# HDMI.net
KiCad netlist of a schematic drawn in Altium Designer
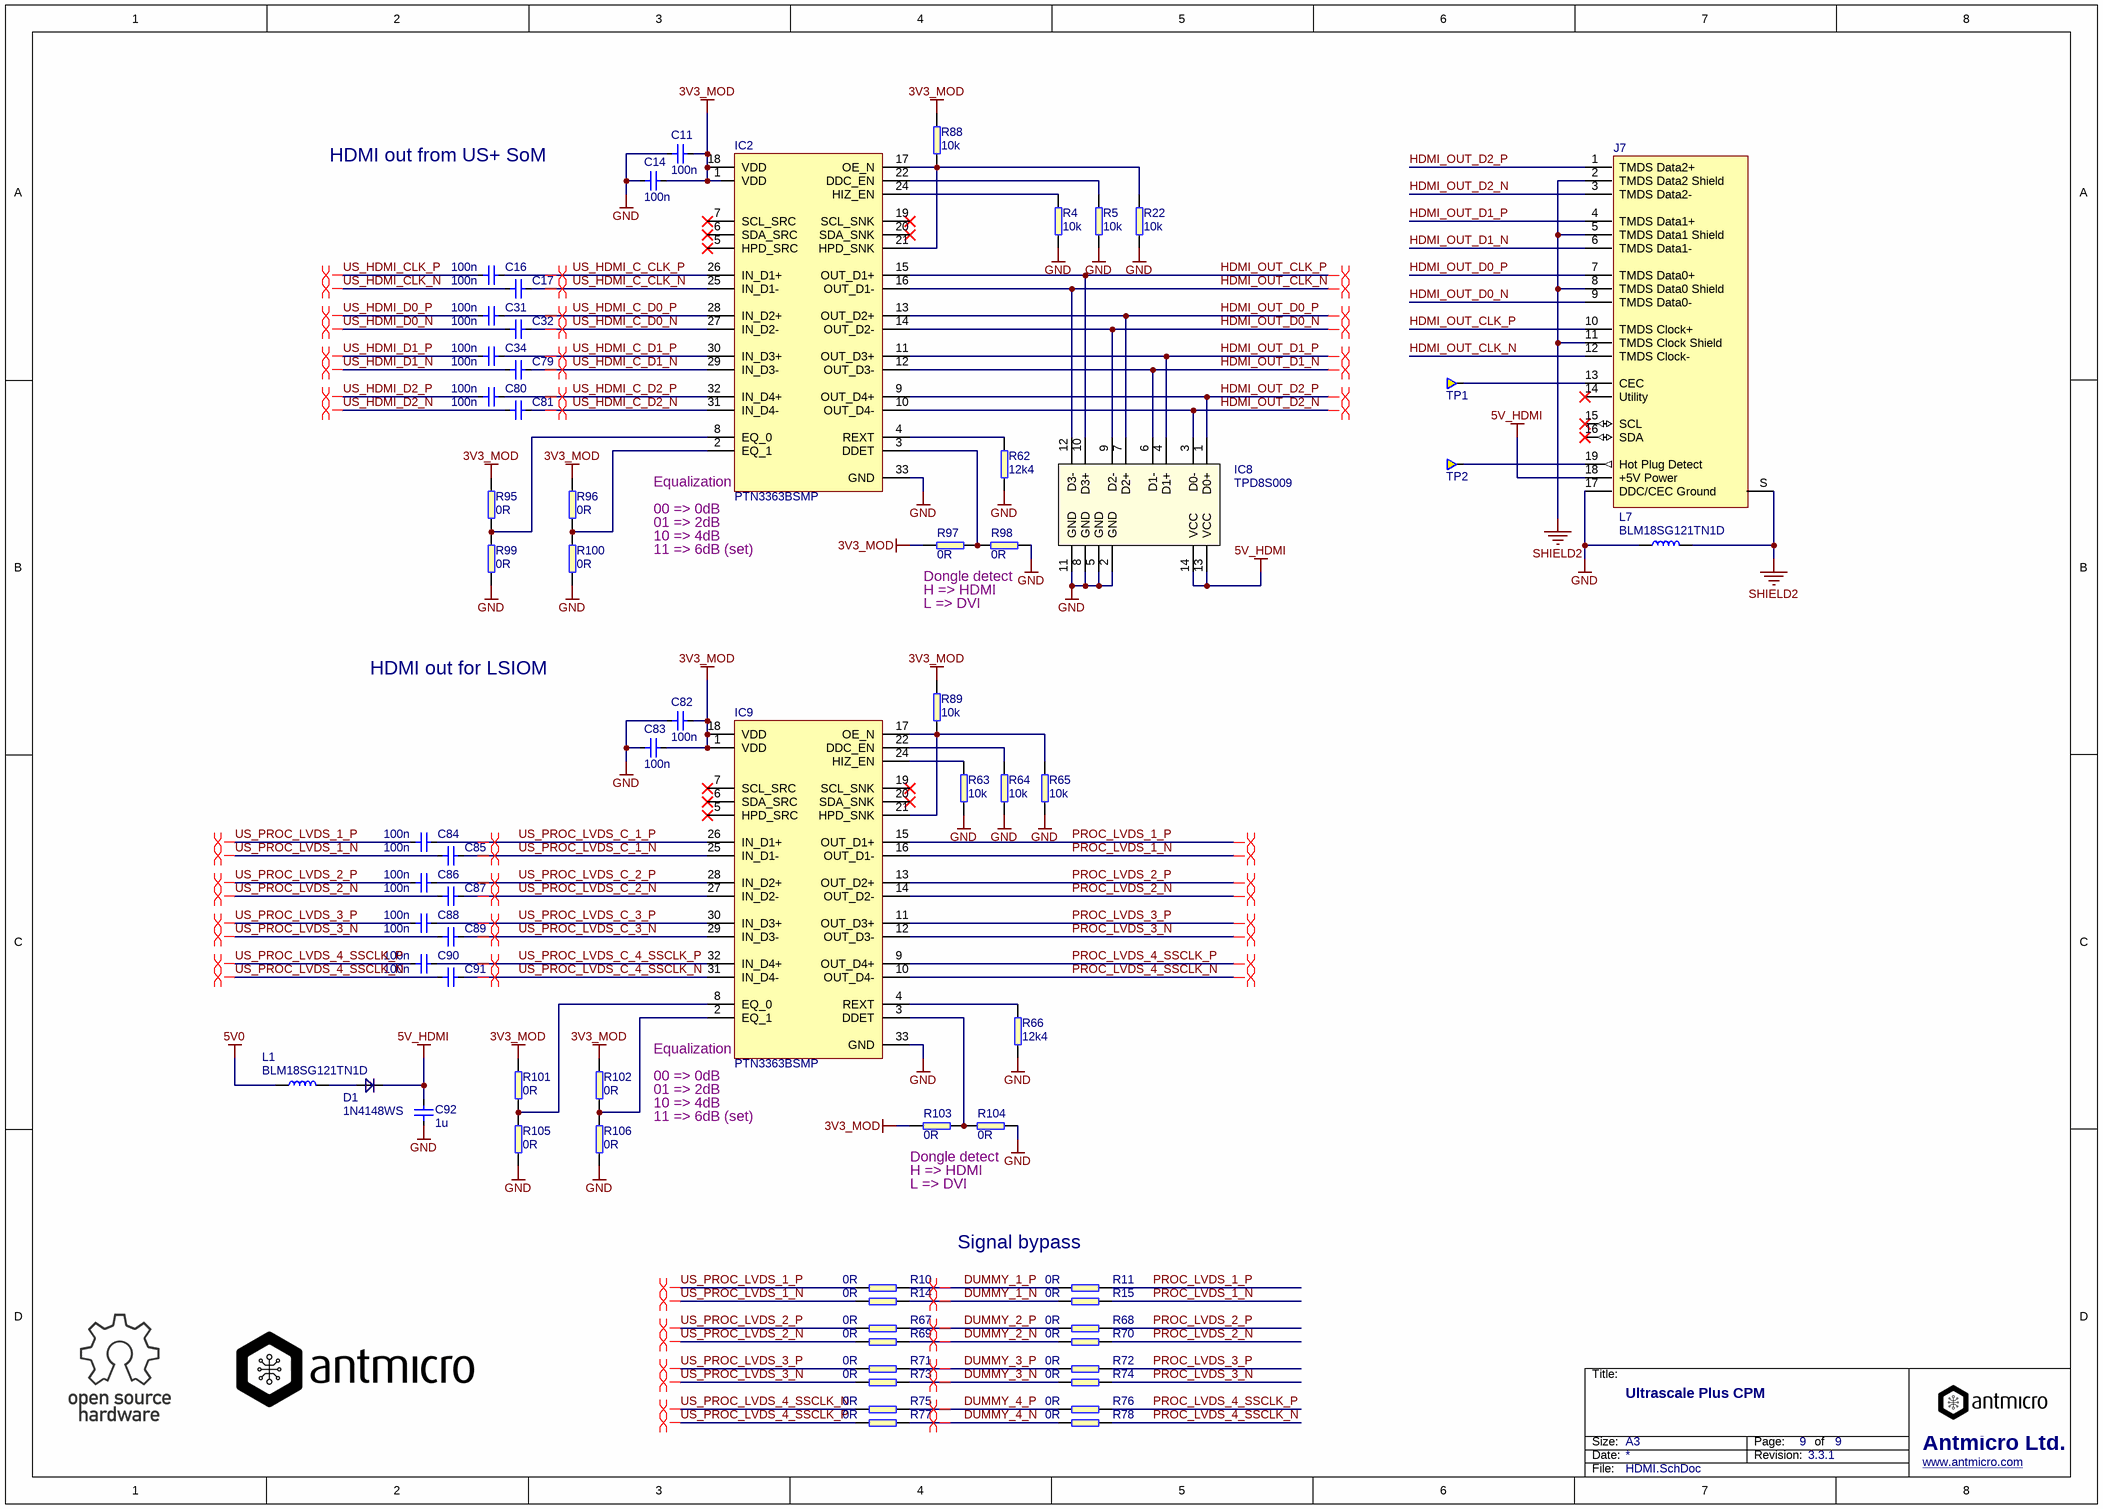
[diagram p0: HDMI.SchDoc]

(export (version "E")
  (design (tool "Eeschema 10.0.6"))
  (components
    (comp (ref "C11")
      (value "100n")
      (footprint "0603")
      (description "MLCC SMT Capacitor 100nF 0603")
      (fields (field (name "PART NUMBER") "C_100n_0603") (field (name "MANUFACTURER") "WALSIN"))
      (libsource (lib "US-Plus-CPM") (part "C"))
    )
    (comp (ref "C14")
      (value "100n")
      (footprint "0603")
      (description "MLCC SMT Capacitor 100nF 0603")
      (fields (field (name "PART NUMBER") "C_100n_0603") (field (name "MANUFACTURER") "WALSIN"))
      (libsource (lib "US-Plus-CPM") (part "C"))
    )
    (comp (ref "C16")
      (value "100n")
      (footprint "0402")
      (description "MLCC SMT Capacitor 100nF 0402")
      (fields (field (name "PART NUMBER") "C_100n_0402") (field (name "MANUFACTURER") "MULTICOMP"))
      (libsource (lib "US-Plus-CPM") (part "C"))
    )
    (comp (ref "C17")
      (value "100n")
      (footprint "0402")
      (description "MLCC SMT Capacitor 100nF 0402")
      (fields (field (name "PART NUMBER") "C_100n_0402") (field (name "MANUFACTURER") "MULTICOMP"))
      (libsource (lib "US-Plus-CPM") (part "C"))
    )
    (comp (ref "C31")
      (value "100n")
      (footprint "0402")
      (description "MLCC SMT Capacitor 100nF 0402")
      (fields (field (name "PART NUMBER") "C_100n_0402") (field (name "MANUFACTURER") "MULTICOMP"))
      (libsource (lib "US-Plus-CPM") (part "C"))
    )
    (comp (ref "C32")
      (value "100n")
      (footprint "0402")
      (description "MLCC SMT Capacitor 100nF 0402")
      (fields (field (name "PART NUMBER") "C_100n_0402") (field (name "MANUFACTURER") "MULTICOMP"))
      (libsource (lib "US-Plus-CPM") (part "C"))
    )
    (comp (ref "C34")
      (value "100n")
      (footprint "0402")
      (description "MLCC SMT Capacitor 100nF 0402")
      (fields (field (name "PART NUMBER") "C_100n_0402") (field (name "MANUFACTURER") "MULTICOMP"))
      (libsource (lib "US-Plus-CPM") (part "C"))
    )
    (comp (ref "C79")
      (value "100n")
      (footprint "0402")
      (description "MLCC SMT Capacitor 100nF 0402")
      (fields (field (name "PART NUMBER") "C_100n_0402") (field (name "MANUFACTURER") "MULTICOMP"))
      (libsource (lib "US-Plus-CPM") (part "C"))
    )
    (comp (ref "C80")
      (value "100n")
      (footprint "0402")
      (description "MLCC SMT Capacitor 100nF 0402")
      (fields (field (name "PART NUMBER") "C_100n_0402") (field (name "MANUFACTURER") "MULTICOMP"))
      (libsource (lib "US-Plus-CPM") (part "C"))
    )
    (comp (ref "C81")
      (value "100n")
      (footprint "0402")
      (description "MLCC SMT Capacitor 100nF 0402")
      (fields (field (name "PART NUMBER") "C_100n_0402") (field (name "MANUFACTURER") "MULTICOMP"))
      (libsource (lib "US-Plus-CPM") (part "C"))
    )
    (comp (ref "C82")
      (value "100n")
      (footprint "0603")
      (description "MLCC SMT Capacitor 100nF 0603")
      (fields (field (name "PART NUMBER") "C_100n_0603") (field (name "MANUFACTURER") "WALSIN"))
      (libsource (lib "US-Plus-CPM") (part "C"))
    )
    (comp (ref "C83")
      (value "100n")
      (footprint "0603")
      (description "MLCC SMT Capacitor 100nF 0603")
      (fields (field (name "PART NUMBER") "C_100n_0603") (field (name "MANUFACTURER") "WALSIN"))
      (libsource (lib "US-Plus-CPM") (part "C"))
    )
    (comp (ref "C84")
      (value "100n")
      (footprint "0402")
      (description "MLCC SMT Capacitor 100nF 0402")
      (fields (field (name "PART NUMBER") "C_100n_0402") (field (name "MANUFACTURER") "MULTICOMP"))
      (libsource (lib "US-Plus-CPM") (part "C"))
    )
    (comp (ref "C85")
      (value "100n")
      (footprint "0402")
      (description "MLCC SMT Capacitor 100nF 0402")
      (fields (field (name "PART NUMBER") "C_100n_0402") (field (name "MANUFACTURER") "MULTICOMP"))
      (libsource (lib "US-Plus-CPM") (part "C"))
    )
    (comp (ref "C86")
      (value "100n")
      (footprint "0402")
      (description "MLCC SMT Capacitor 100nF 0402")
      (fields (field (name "PART NUMBER") "C_100n_0402") (field (name "MANUFACTURER") "MULTICOMP"))
      (libsource (lib "US-Plus-CPM") (part "C"))
    )
    (comp (ref "C87")
      (value "100n")
      (footprint "0402")
      (description "MLCC SMT Capacitor 100nF 0402")
      (fields (field (name "PART NUMBER") "C_100n_0402") (field (name "MANUFACTURER") "MULTICOMP"))
      (libsource (lib "US-Plus-CPM") (part "C"))
    )
    (comp (ref "C88")
      (value "100n")
      (footprint "0402")
      (description "MLCC SMT Capacitor 100nF 0402")
      (fields (field (name "PART NUMBER") "C_100n_0402") (field (name "MANUFACTURER") "MULTICOMP"))
      (libsource (lib "US-Plus-CPM") (part "C"))
    )
    (comp (ref "C89")
      (value "100n")
      (footprint "0402")
      (description "MLCC SMT Capacitor 100nF 0402")
      (fields (field (name "PART NUMBER") "C_100n_0402") (field (name "MANUFACTURER") "MULTICOMP"))
      (libsource (lib "US-Plus-CPM") (part "C"))
    )
    (comp (ref "C90")
      (value "100n")
      (footprint "0402")
      (description "MLCC SMT Capacitor 100nF 0402")
      (fields (field (name "PART NUMBER") "C_100n_0402") (field (name "MANUFACTURER") "MULTICOMP"))
      (libsource (lib "US-Plus-CPM") (part "C"))
    )
    (comp (ref "C91")
      (value "100n")
      (footprint "0402")
      (description "MLCC SMT Capacitor 100nF 0402")
      (fields (field (name "PART NUMBER") "C_100n_0402") (field (name "MANUFACTURER") "MULTICOMP"))
      (libsource (lib "US-Plus-CPM") (part "C"))
    )
    (comp (ref "C92")
      (value "1u")
      (footprint "0603")
      (description "MLCC SMT Capacitor 1uF 0603")
      (fields (field (name "PART NUMBER") "C_1u_0603") (field (name "MANUFACTURER") "MULTICOMP"))
      (libsource (lib "US-Plus-CPM") (part "C"))
    )
    (comp (ref "D1")
      (value "1N4148WS")
      (footprint "SOD-323")
      (description "Diode small signal")
      (fields (field (name "MANUFACTURER") "MULTICOMP"))
      (libsource (lib "US-Plus-CPM") (part "diode"))
    )
    (comp (ref "IC2")
      (value "PTN3363BSMP")
      (footprint "QFN-32")
      (description "HDMI level shifter")
      (fields (field (name "MANUFACTURER") "NXP"))
      (libsource (lib "US-Plus-CPM") (part "PTN3363"))
    )
    (comp (ref "IC8")
      (value "TPD8S009")
      (footprint "SON-15")
      (description "8-Channel ESD Protection for DisplayPort and HDMI")
      (fields (field (name "MANUFACTURER") "TEXAS INSTRUMENTS") (field (name "MPN") "TPD8S009DSMR"))
      (libsource (lib "US-Plus-CPM") (part "TPD8S009"))
    )
    (comp (ref "IC9")
      (value "PTN3363BSMP")
      (footprint "QFN-32")
      (description "HDMI level shifter")
      (fields (field (name "MANUFACTURER") "NXP"))
      (libsource (lib "US-Plus-CPM") (part "PTN3363"))
    )
    (comp (ref "J7")
      (value "~")
      (footprint "Molex_HDMI_471511001")
      (description "Header right angle HDMI")
      (fields (field (name "PART NUMBER") "CON-Molex-471511001") (field (name "MANUFACTURER") "MOLEX"))
      (libsource (lib "US-Plus-CPM") (part "CON-Molex-471511001"))
    )
    (comp (ref "L1")
      (value "BLM18SG121TN1D")
      (footprint "0603")
      (description "FERRITE BEAD, 0.025OHM, 3A, 0603")
      (fields (field (name "MANUFACTURER") "MURATA"))
      (libsource (lib "US-Plus-CPM") (part "Inductor SMT"))
    )
    (comp (ref "L7")
      (value "BLM18SG121TN1D")
      (footprint "0603")
      (description "FERRITE BEAD, 0.025OHM, 3A, 0603")
      (fields (field (name "MANUFACTURER") "MURATA"))
      (libsource (lib "US-Plus-CPM") (part "Inductor SMT"))
    )
    (comp (ref "R4")
      (value "10k")
      (footprint "0402")
      (description "SMT Resistor 0402")
      (fields (field (name "PART NUMBER") "R_10k_0402") (field (name "MANUFACTURER") "MULTICOMP"))
      (libsource (lib "") (part "R_1"))
    )
    (comp (ref "R5")
      (value "10k")
      (footprint "0402")
      (description "SMT Resistor 0402")
      (fields (field (name "PART NUMBER") "R_10k_0402") (field (name "MANUFACTURER") "MULTICOMP"))
      (libsource (lib "") (part "R_1"))
    )
    (comp (ref "R10")
      (value "0R")
      (footprint "0402")
      (description "SMT Resistor 0402")
      (fields (field (name "PART NUMBER") "R_0R_0402") (field (name "MANUFACTURER") "MULTICOMP"))
      (libsource (lib "US-Plus-CPM") (part "R"))
    )
    (comp (ref "R11")
      (value "0R")
      (footprint "0402")
      (description "SMT Resistor 0402")
      (fields (field (name "PART NUMBER") "R_0R_0402") (field (name "MANUFACTURER") "MULTICOMP"))
      (libsource (lib "US-Plus-CPM") (part "R"))
    )
    (comp (ref "R14")
      (value "0R")
      (footprint "0402")
      (description "SMT Resistor 0402")
      (fields (field (name "PART NUMBER") "R_0R_0402") (field (name "MANUFACTURER") "MULTICOMP"))
      (libsource (lib "US-Plus-CPM") (part "R"))
    )
    (comp (ref "R15")
      (value "0R")
      (footprint "0402")
      (description "SMT Resistor 0402")
      (fields (field (name "PART NUMBER") "R_0R_0402") (field (name "MANUFACTURER") "MULTICOMP"))
      (libsource (lib "US-Plus-CPM") (part "R"))
    )
    (comp (ref "R22")
      (value "10k")
      (footprint "0402")
      (description "SMT Resistor 0402")
      (fields (field (name "PART NUMBER") "R_10k_0402") (field (name "MANUFACTURER") "MULTICOMP"))
      (libsource (lib "") (part "R_1"))
    )
    (comp (ref "R62")
      (value "12k4")
      (footprint "0603")
      (description "SMT Resistor 12k4 0603 1%")
      (fields (field (name "PART NUMBER") "R_12k4_0603_1%") (field (name "MANUFACTURER") "Vishay"))
      (libsource (lib "") (part "R_2"))
    )
    (comp (ref "R63")
      (value "10k")
      (footprint "0402")
      (description "SMT Resistor 0402")
      (fields (field (name "PART NUMBER") "R_10k_0402") (field (name "MANUFACTURER") "MULTICOMP"))
      (libsource (lib "") (part "R_1"))
    )
    (comp (ref "R64")
      (value "10k")
      (footprint "0402")
      (description "SMT Resistor 0402")
      (fields (field (name "PART NUMBER") "R_10k_0402") (field (name "MANUFACTURER") "MULTICOMP"))
      (libsource (lib "") (part "R_1"))
    )
    (comp (ref "R65")
      (value "10k")
      (footprint "0402")
      (description "SMT Resistor 0402")
      (fields (field (name "PART NUMBER") "R_10k_0402") (field (name "MANUFACTURER") "MULTICOMP"))
      (libsource (lib "") (part "R_1"))
    )
    (comp (ref "R66")
      (value "12k4")
      (footprint "0603")
      (description "SMT Resistor 12k4 0603 1%")
      (fields (field (name "PART NUMBER") "R_12k4_0603_1%") (field (name "MANUFACTURER") "Vishay"))
      (libsource (lib "") (part "R_2"))
    )
    (comp (ref "R67")
      (value "0R")
      (footprint "0402")
      (description "SMT Resistor 0402")
      (fields (field (name "PART NUMBER") "R_0R_0402") (field (name "MANUFACTURER") "MULTICOMP"))
      (libsource (lib "US-Plus-CPM") (part "R"))
    )
    (comp (ref "R68")
      (value "0R")
      (footprint "0402")
      (description "SMT Resistor 0402")
      (fields (field (name "PART NUMBER") "R_0R_0402") (field (name "MANUFACTURER") "MULTICOMP"))
      (libsource (lib "US-Plus-CPM") (part "R"))
    )
    (comp (ref "R69")
      (value "0R")
      (footprint "0402")
      (description "SMT Resistor 0402")
      (fields (field (name "PART NUMBER") "R_0R_0402") (field (name "MANUFACTURER") "MULTICOMP"))
      (libsource (lib "US-Plus-CPM") (part "R"))
    )
    (comp (ref "R70")
      (value "0R")
      (footprint "0402")
      (description "SMT Resistor 0402")
      (fields (field (name "PART NUMBER") "R_0R_0402") (field (name "MANUFACTURER") "MULTICOMP"))
      (libsource (lib "US-Plus-CPM") (part "R"))
    )
    (comp (ref "R71")
      (value "0R")
      (footprint "0402")
      (description "SMT Resistor 0402")
      (fields (field (name "PART NUMBER") "R_0R_0402") (field (name "MANUFACTURER") "MULTICOMP"))
      (libsource (lib "US-Plus-CPM") (part "R"))
    )
    (comp (ref "R72")
      (value "0R")
      (footprint "0402")
      (description "SMT Resistor 0402")
      (fields (field (name "PART NUMBER") "R_0R_0402") (field (name "MANUFACTURER") "MULTICOMP"))
      (libsource (lib "US-Plus-CPM") (part "R"))
    )
    (comp (ref "R73")
      (value "0R")
      (footprint "0402")
      (description "SMT Resistor 0402")
      (fields (field (name "PART NUMBER") "R_0R_0402") (field (name "MANUFACTURER") "MULTICOMP"))
      (libsource (lib "US-Plus-CPM") (part "R"))
    )
    (comp (ref "R74")
      (value "0R")
      (footprint "0402")
      (description "SMT Resistor 0402")
      (fields (field (name "PART NUMBER") "R_0R_0402") (field (name "MANUFACTURER") "MULTICOMP"))
      (libsource (lib "US-Plus-CPM") (part "R"))
    )
    (comp (ref "R75")
      (value "0R")
      (footprint "0402")
      (description "SMT Resistor 0402")
      (fields (field (name "PART NUMBER") "R_0R_0402") (field (name "MANUFACTURER") "MULTICOMP"))
      (libsource (lib "US-Plus-CPM") (part "R"))
    )
    (comp (ref "R76")
      (value "0R")
      (footprint "0402")
      (description "SMT Resistor 0402")
      (fields (field (name "PART NUMBER") "R_0R_0402") (field (name "MANUFACTURER") "MULTICOMP"))
      (libsource (lib "US-Plus-CPM") (part "R"))
    )
    (comp (ref "R77")
      (value "0R")
      (footprint "0402")
      (description "SMT Resistor 0402")
      (fields (field (name "PART NUMBER") "R_0R_0402") (field (name "MANUFACTURER") "MULTICOMP"))
      (libsource (lib "US-Plus-CPM") (part "R"))
    )
    (comp (ref "R78")
      (value "0R")
      (footprint "0402")
      (description "SMT Resistor 0402")
      (fields (field (name "PART NUMBER") "R_0R_0402") (field (name "MANUFACTURER") "MULTICOMP"))
      (libsource (lib "US-Plus-CPM") (part "R"))
    )
    (comp (ref "R88")
      (value "10k")
      (footprint "0402")
      (description "SMT Resistor 0402")
      (fields (field (name "PART NUMBER") "R_10k_0402") (field (name "MANUFACTURER") "MULTICOMP"))
      (libsource (lib "") (part "R_1"))
    )
    (comp (ref "R89")
      (value "10k")
      (footprint "0402")
      (description "SMT Resistor 0402")
      (fields (field (name "PART NUMBER") "R_10k_0402") (field (name "MANUFACTURER") "MULTICOMP"))
      (libsource (lib "") (part "R_1"))
    )
    (comp (ref "R95")
      (value "0R")
      (footprint "0402")
      (description "SMT Resistor 0402")
      (fields (field (name "MANUFACTURER") "MULTICOMP") (field (name "PART NUMBER") "R_0R_0402"))
      (libsource (lib "") (part "R_2"))
    )
    (comp (ref "R96")
      (value "0R")
      (footprint "0402")
      (description "SMT Resistor 0402")
      (fields (field (name "MANUFACTURER") "MULTICOMP") (field (name "PART NUMBER") "R_0R_0402"))
      (libsource (lib "") (part "R_2"))
    )
    (comp (ref "R97")
      (value "0R")
      (footprint "0402")
      (description "SMT Resistor 0402")
      (fields (field (name "MANUFACTURER") "MULTICOMP") (field (name "PART NUMBER") "R_0R_0402"))
      (libsource (lib "") (part "R_3"))
    )
    (comp (ref "R98")
      (value "0R")
      (footprint "0402")
      (description "SMT Resistor 0402")
      (fields (field (name "MANUFACTURER") "MULTICOMP") (field (name "PART NUMBER") "R_0R_0402"))
      (libsource (lib "") (part "R_3"))
    )
    (comp (ref "R99")
      (value "0R")
      (footprint "0402")
      (description "SMT Resistor 0402")
      (fields (field (name "MANUFACTURER") "MULTICOMP") (field (name "PART NUMBER") "R_0R_0402"))
      (libsource (lib "") (part "R_2"))
    )
    (comp (ref "R100")
      (value "0R")
      (footprint "0402")
      (description "SMT Resistor 0402")
      (fields (field (name "MANUFACTURER") "MULTICOMP") (field (name "PART NUMBER") "R_0R_0402"))
      (libsource (lib "") (part "R_2"))
    )
    (comp (ref "R101")
      (value "0R")
      (footprint "0402")
      (description "SMT Resistor 0402")
      (fields (field (name "MANUFACTURER") "MULTICOMP") (field (name "PART NUMBER") "R_0R_0402"))
      (libsource (lib "") (part "R_2"))
    )
    (comp (ref "R102")
      (value "0R")
      (footprint "0402")
      (description "SMT Resistor 0402")
      (fields (field (name "MANUFACTURER") "MULTICOMP") (field (name "PART NUMBER") "R_0R_0402"))
      (libsource (lib "") (part "R_2"))
    )
    (comp (ref "R103")
      (value "0R")
      (footprint "0402")
      (description "SMT Resistor 0402")
      (fields (field (name "MANUFACTURER") "MULTICOMP") (field (name "PART NUMBER") "R_0R_0402"))
      (libsource (lib "") (part "R_3"))
    )
    (comp (ref "R104")
      (value "0R")
      (footprint "0402")
      (description "SMT Resistor 0402")
      (fields (field (name "MANUFACTURER") "MULTICOMP") (field (name "PART NUMBER") "R_0R_0402"))
      (libsource (lib "") (part "R_3"))
    )
    (comp (ref "R105")
      (value "0R")
      (footprint "0402")
      (description "SMT Resistor 0402")
      (fields (field (name "MANUFACTURER") "MULTICOMP") (field (name "PART NUMBER") "R_0R_0402"))
      (libsource (lib "") (part "R_2"))
    )
    (comp (ref "R106")
      (value "0R")
      (footprint "0402")
      (description "SMT Resistor 0402")
      (fields (field (name "MANUFACTURER") "MULTICOMP") (field (name "PART NUMBER") "R_0R_0402"))
      (libsource (lib "") (part "R_2"))
    )
    (comp (ref "TP1")
      (value "*")
      (footprint "Testpad")
      (description "Testpad 2mm diameter")
      (fields (field (name "PART NUMBER") "Testpad"))
      (libsource (lib "US-Plus-CPM") (part "Testpad"))
    )
    (comp (ref "TP2")
      (value "*")
      (footprint "Testpad")
      (description "Testpad 2mm diameter")
      (fields (field (name "PART NUMBER") "Testpad"))
      (libsource (lib "US-Plus-CPM") (part "Testpad"))
    )
  )
  (nets
    (net (code "1") (name "/DUMMY_1_N") (class "Default")
      (node (ref "R14") (pin "2") (pintype "passive"))
      (node (ref "R15") (pin "1") (pintype "passive"))
    )
    (net (code "2") (name "/DUMMY_1_P") (class "Default")
      (node (ref "R10") (pin "2") (pintype "passive"))
      (node (ref "R11") (pin "1") (pintype "passive"))
    )
    (net (code "3") (name "/DUMMY_2_N") (class "Default")
      (node (ref "R69") (pin "2") (pintype "passive"))
      (node (ref "R70") (pin "1") (pintype "passive"))
    )
    (net (code "4") (name "/DUMMY_2_P") (class "Default")
      (node (ref "R67") (pin "2") (pintype "passive"))
      (node (ref "R68") (pin "1") (pintype "passive"))
    )
    (net (code "5") (name "/DUMMY_3_N") (class "Default")
      (node (ref "R73") (pin "2") (pintype "passive"))
      (node (ref "R74") (pin "1") (pintype "passive"))
    )
    (net (code "6") (name "/DUMMY_3_P") (class "Default")
      (node (ref "R71") (pin "2") (pintype "passive"))
      (node (ref "R72") (pin "1") (pintype "passive"))
    )
    (net (code "7") (name "/DUMMY_4_N") (class "Default")
      (node (ref "R77") (pin "2") (pintype "passive"))
      (node (ref "R78") (pin "1") (pintype "passive"))
    )
    (net (code "8") (name "/DUMMY_4_P") (class "Default")
      (node (ref "R75") (pin "2") (pintype "passive"))
      (node (ref "R76") (pin "1") (pintype "passive"))
    )
    (net (code "9") (name "/HDMI_OUT_CLK_N") (class "Default")
      (node (ref "IC2") (pin "16") (pinfunction "OUT_D1-_16") (pintype "passive"))
      (node (ref "IC8") (pin "12") (pinfunction "D3-_12") (pintype "passive"))
      (node (ref "J7") (pin "12") (pinfunction "TMDS_Clock-_12") (pintype "passive"))
    )
    (net (code "10") (name "/HDMI_OUT_CLK_P") (class "Default")
      (node (ref "IC2") (pin "15") (pinfunction "OUT_D1+_15") (pintype "passive"))
      (node (ref "IC8") (pin "10") (pinfunction "D3+_10") (pintype "passive"))
      (node (ref "J7") (pin "10") (pinfunction "TMDS_Clock+_10") (pintype "passive"))
    )
    (net (code "11") (name "/HDMI_OUT_D0_N") (class "Default")
      (node (ref "IC2") (pin "14") (pinfunction "OUT_D2-_14") (pintype "passive"))
      (node (ref "IC8") (pin "9") (pinfunction "D2-_9") (pintype "passive"))
      (node (ref "J7") (pin "9") (pinfunction "TMDS_Data0-_9") (pintype "passive"))
    )
    (net (code "12") (name "/HDMI_OUT_D0_P") (class "Default")
      (node (ref "IC2") (pin "13") (pinfunction "OUT_D2+_13") (pintype "passive"))
      (node (ref "IC8") (pin "7") (pinfunction "D2+_7") (pintype "passive"))
      (node (ref "J7") (pin "7") (pinfunction "TMDS_Data0+_7") (pintype "passive"))
    )
    (net (code "13") (name "/HDMI_OUT_D1_N") (class "Default")
      (node (ref "IC2") (pin "12") (pinfunction "OUT_D3-_12") (pintype "passive"))
      (node (ref "IC8") (pin "6") (pinfunction "D1-_6") (pintype "passive"))
      (node (ref "J7") (pin "6") (pinfunction "TMDS_Data1-_6") (pintype "passive"))
    )
    (net (code "14") (name "/HDMI_OUT_D1_P") (class "Default")
      (node (ref "IC2") (pin "11") (pinfunction "OUT_D3+_11") (pintype "passive"))
      (node (ref "IC8") (pin "4") (pinfunction "D1+_4") (pintype "passive"))
      (node (ref "J7") (pin "4") (pinfunction "TMDS_Data1+_4") (pintype "passive"))
    )
    (net (code "15") (name "/HDMI_OUT_D2_N") (class "Default")
      (node (ref "IC2") (pin "10") (pinfunction "OUT_D4-_10") (pintype "passive"))
      (node (ref "IC8") (pin "3") (pinfunction "D0-_3") (pintype "passive"))
      (node (ref "J7") (pin "3") (pinfunction "TMDS_Data2-_3") (pintype "passive"))
    )
    (net (code "16") (name "/HDMI_OUT_D2_P") (class "Default")
      (node (ref "IC2") (pin "9") (pinfunction "OUT_D4+_9") (pintype "passive"))
      (node (ref "IC8") (pin "1") (pinfunction "D0+_1") (pintype "passive"))
      (node (ref "J7") (pin "1") (pinfunction "TMDS_Data2+_1") (pintype "passive"))
    )
    (net (code "17") (name "/PROC_LVDS_1_N") (class "Default")
      (node (ref "IC9") (pin "16") (pinfunction "OUT_D1-_16") (pintype "passive"))
      (node (ref "R15") (pin "2") (pintype "passive"))
    )
    (net (code "18") (name "/PROC_LVDS_1_P") (class "Default")
      (node (ref "IC9") (pin "15") (pinfunction "OUT_D1+_15") (pintype "passive"))
      (node (ref "R11") (pin "2") (pintype "passive"))
    )
    (net (code "19") (name "/PROC_LVDS_2_N") (class "Default")
      (node (ref "IC9") (pin "14") (pinfunction "OUT_D2-_14") (pintype "passive"))
      (node (ref "R70") (pin "2") (pintype "passive"))
    )
    (net (code "20") (name "/PROC_LVDS_2_P") (class "Default")
      (node (ref "IC9") (pin "13") (pinfunction "OUT_D2+_13") (pintype "passive"))
      (node (ref "R68") (pin "2") (pintype "passive"))
    )
    (net (code "21") (name "/PROC_LVDS_3_N") (class "Default")
      (node (ref "IC9") (pin "12") (pinfunction "OUT_D3-_12") (pintype "passive"))
      (node (ref "R74") (pin "2") (pintype "passive"))
    )
    (net (code "22") (name "/PROC_LVDS_3_P") (class "Default")
      (node (ref "IC9") (pin "11") (pinfunction "OUT_D3+_11") (pintype "passive"))
      (node (ref "R72") (pin "2") (pintype "passive"))
    )
    (net (code "23") (name "/PROC_LVDS_4_SSCLK_N") (class "Default")
      (node (ref "IC9") (pin "10") (pinfunction "OUT_D4-_10") (pintype "passive"))
      (node (ref "R78") (pin "2") (pintype "passive"))
    )
    (net (code "24") (name "/PROC_LVDS_4_SSCLK_P") (class "Default")
      (node (ref "IC9") (pin "9") (pinfunction "OUT_D4+_9") (pintype "passive"))
      (node (ref "R76") (pin "2") (pintype "passive"))
    )
    (net (code "25") (name "/US_HDMI_CLK_N") (class "Default")
      (node (ref "C17") (pin "1") (pinfunction "1_1") (pintype "passive"))
    )
    (net (code "26") (name "/US_HDMI_CLK_P") (class "Default")
      (node (ref "C16") (pin "1") (pinfunction "1_1") (pintype "passive"))
    )
    (net (code "27") (name "/US_HDMI_C_CLK_N") (class "Default")
      (node (ref "C17") (pin "2") (pinfunction "2_2") (pintype "passive"))
      (node (ref "IC2") (pin "25") (pinfunction "IN_D1-_25") (pintype "passive"))
    )
    (net (code "28") (name "/US_HDMI_C_CLK_P") (class "Default")
      (node (ref "C16") (pin "2") (pinfunction "2_2") (pintype "passive"))
      (node (ref "IC2") (pin "26") (pinfunction "IN_D1+_26") (pintype "passive"))
    )
    (net (code "29") (name "/US_HDMI_C_D0_N") (class "Default")
      (node (ref "C32") (pin "2") (pinfunction "2_2") (pintype "passive"))
      (node (ref "IC2") (pin "27") (pinfunction "IN_D2-_27") (pintype "passive"))
    )
    (net (code "30") (name "/US_HDMI_C_D0_P") (class "Default")
      (node (ref "C31") (pin "2") (pinfunction "2_2") (pintype "passive"))
      (node (ref "IC2") (pin "28") (pinfunction "IN_D2+_28") (pintype "passive"))
    )
    (net (code "31") (name "/US_HDMI_C_D1_N") (class "Default")
      (node (ref "C79") (pin "2") (pinfunction "2_2") (pintype "passive"))
      (node (ref "IC2") (pin "29") (pinfunction "IN_D3-_29") (pintype "passive"))
    )
    (net (code "32") (name "/US_HDMI_C_D1_P") (class "Default")
      (node (ref "C34") (pin "2") (pinfunction "2_2") (pintype "passive"))
      (node (ref "IC2") (pin "30") (pinfunction "IN_D3+_30") (pintype "passive"))
    )
    (net (code "33") (name "/US_HDMI_C_D2_N") (class "Default")
      (node (ref "C81") (pin "2") (pinfunction "2_2") (pintype "passive"))
      (node (ref "IC2") (pin "31") (pinfunction "IN_D4-_31") (pintype "passive"))
    )
    (net (code "34") (name "/US_HDMI_C_D2_P") (class "Default")
      (node (ref "C80") (pin "2") (pinfunction "2_2") (pintype "passive"))
      (node (ref "IC2") (pin "32") (pinfunction "IN_D4+_32") (pintype "passive"))
    )
    (net (code "35") (name "/US_HDMI_D0_N") (class "Default")
      (node (ref "C32") (pin "1") (pinfunction "1_1") (pintype "passive"))
    )
    (net (code "36") (name "/US_HDMI_D0_P") (class "Default")
      (node (ref "C31") (pin "1") (pinfunction "1_1") (pintype "passive"))
    )
    (net (code "37") (name "/US_HDMI_D1_N") (class "Default")
      (node (ref "C79") (pin "1") (pinfunction "1_1") (pintype "passive"))
    )
    (net (code "38") (name "/US_HDMI_D1_P") (class "Default")
      (node (ref "C34") (pin "1") (pinfunction "1_1") (pintype "passive"))
    )
    (net (code "39") (name "/US_HDMI_D2_N") (class "Default")
      (node (ref "C81") (pin "1") (pinfunction "1_1") (pintype "passive"))
    )
    (net (code "40") (name "/US_HDMI_D2_P") (class "Default")
      (node (ref "C80") (pin "1") (pinfunction "1_1") (pintype "passive"))
    )
    (net (code "41") (name "/US_PROC_LVDS_1_N") (class "Default")
      (node (ref "C85") (pin "1") (pinfunction "1_1") (pintype "passive"))
      (node (ref "R14") (pin "1") (pintype "passive"))
    )
    (net (code "42") (name "/US_PROC_LVDS_1_P") (class "Default")
      (node (ref "C84") (pin "1") (pinfunction "1_1") (pintype "passive"))
      (node (ref "R10") (pin "1") (pintype "passive"))
    )
    (net (code "43") (name "/US_PROC_LVDS_2_N") (class "Default")
      (node (ref "C87") (pin "1") (pinfunction "1_1") (pintype "passive"))
      (node (ref "R69") (pin "1") (pintype "passive"))
    )
    (net (code "44") (name "/US_PROC_LVDS_2_P") (class "Default")
      (node (ref "C86") (pin "1") (pinfunction "1_1") (pintype "passive"))
      (node (ref "R67") (pin "1") (pintype "passive"))
    )
    (net (code "45") (name "/US_PROC_LVDS_3_N") (class "Default")
      (node (ref "C89") (pin "1") (pinfunction "1_1") (pintype "passive"))
      (node (ref "R73") (pin "1") (pintype "passive"))
    )
    (net (code "46") (name "/US_PROC_LVDS_3_P") (class "Default")
      (node (ref "C88") (pin "1") (pinfunction "1_1") (pintype "passive"))
      (node (ref "R71") (pin "1") (pintype "passive"))
    )
    (net (code "47") (name "/US_PROC_LVDS_4_SSCLK_N") (class "Default")
      (node (ref "C91") (pin "1") (pinfunction "1_1") (pintype "passive"))
      (node (ref "R75") (pin "1") (pintype "passive"))
    )
    (net (code "48") (name "/US_PROC_LVDS_4_SSCLK_P") (class "Default")
      (node (ref "C90") (pin "1") (pinfunction "1_1") (pintype "passive"))
      (node (ref "R77") (pin "1") (pintype "passive"))
    )
    (net (code "49") (name "/US_PROC_LVDS_C_1_N") (class "Default")
      (node (ref "C85") (pin "2") (pinfunction "2_2") (pintype "passive"))
      (node (ref "IC9") (pin "25") (pinfunction "IN_D1-_25") (pintype "passive"))
    )
    (net (code "50") (name "/US_PROC_LVDS_C_1_P") (class "Default")
      (node (ref "C84") (pin "2") (pinfunction "2_2") (pintype "passive"))
      (node (ref "IC9") (pin "26") (pinfunction "IN_D1+_26") (pintype "passive"))
    )
    (net (code "51") (name "/US_PROC_LVDS_C_2_N") (class "Default")
      (node (ref "C87") (pin "2") (pinfunction "2_2") (pintype "passive"))
      (node (ref "IC9") (pin "27") (pinfunction "IN_D2-_27") (pintype "passive"))
    )
    (net (code "52") (name "/US_PROC_LVDS_C_2_P") (class "Default")
      (node (ref "C86") (pin "2") (pinfunction "2_2") (pintype "passive"))
      (node (ref "IC9") (pin "28") (pinfunction "IN_D2+_28") (pintype "passive"))
    )
    (net (code "53") (name "/US_PROC_LVDS_C_3_N") (class "Default")
      (node (ref "C89") (pin "2") (pinfunction "2_2") (pintype "passive"))
      (node (ref "IC9") (pin "29") (pinfunction "IN_D3-_29") (pintype "passive"))
    )
    (net (code "54") (name "/US_PROC_LVDS_C_3_P") (class "Default")
      (node (ref "C88") (pin "2") (pinfunction "2_2") (pintype "passive"))
      (node (ref "IC9") (pin "30") (pinfunction "IN_D3+_30") (pintype "passive"))
    )
    (net (code "55") (name "/US_PROC_LVDS_C_4_SSCLK_N") (class "Default")
      (node (ref "C91") (pin "2") (pinfunction "2_2") (pintype "passive"))
      (node (ref "IC9") (pin "31") (pinfunction "IN_D4-_31") (pintype "passive"))
    )
    (net (code "56") (name "/US_PROC_LVDS_C_4_SSCLK_P") (class "Default")
      (node (ref "C90") (pin "2") (pinfunction "2_2") (pintype "passive"))
      (node (ref "IC9") (pin "32") (pinfunction "IN_D4+_32") (pintype "passive"))
    )
    (net (code "57") (name "3V3_MOD") (class "Default")
      (node (ref "C11") (pin "2") (pinfunction "2_2") (pintype "passive"))
      (node (ref "C14") (pin "2") (pinfunction "2_2") (pintype "passive"))
      (node (ref "C82") (pin "2") (pinfunction "2_2") (pintype "passive"))
      (node (ref "C83") (pin "2") (pinfunction "2_2") (pintype "passive"))
      (node (ref "IC2") (pin "1") (pinfunction "VDD_1") (pintype "passive"))
      (node (ref "IC2") (pin "18") (pinfunction "VDD_18") (pintype "passive"))
      (node (ref "IC9") (pin "1") (pinfunction "VDD_1") (pintype "passive"))
      (node (ref "IC9") (pin "18") (pinfunction "VDD_18") (pintype "passive"))
      (node (ref "R101") (pin "2") (pintype "passive"))
      (node (ref "R102") (pin "2") (pintype "passive"))
      (node (ref "R103") (pin "2") (pintype "passive"))
      (node (ref "R88") (pin "1") (pintype "passive"))
      (node (ref "R89") (pin "1") (pintype "passive"))
      (node (ref "R95") (pin "2") (pintype "passive"))
      (node (ref "R96") (pin "2") (pintype "passive"))
      (node (ref "R97") (pin "2") (pintype "passive"))
    )
    (net (code "58") (name "5V0") (class "Default") (node (ref "L1") (pin "1") (pintype "passive")))
    (net (code "59") (name "5V_HDMI") (class "Default")
      (node (ref "C92") (pin "2") (pinfunction "2_2") (pintype "passive"))
      (node (ref "D1") (pin "C") (pinfunction "C_C") (pintype "passive"))
      (node (ref "IC8") (pin "13") (pinfunction "VCC_13") (pintype "passive"))
      (node (ref "IC8") (pin "14") (pinfunction "VCC_14") (pintype "passive"))
      (node (ref "J7") (pin "18") (pinfunction "+5V_Power_18") (pintype "power_in"))
    )
    (net (code "60") (name "GND") (class "Default")
      (node (ref "C11") (pin "1") (pinfunction "1_1") (pintype "passive"))
      (node (ref "C14") (pin "1") (pinfunction "1_1") (pintype "passive"))
      (node (ref "C82") (pin "1") (pinfunction "1_1") (pintype "passive"))
      (node (ref "C83") (pin "1") (pinfunction "1_1") (pintype "passive"))
      (node (ref "C92") (pin "1") (pinfunction "1_1") (pintype "passive"))
      (node (ref "IC2") (pin "33") (pinfunction "GND_33") (pintype "passive"))
      (node (ref "IC8") (pin "11") (pinfunction "GND_11") (pintype "passive"))
      (node (ref "IC8") (pin "2") (pinfunction "GND_2") (pintype "passive"))
      (node (ref "IC8") (pin "5") (pinfunction "GND_5") (pintype "passive"))
      (node (ref "IC8") (pin "8") (pinfunction "GND_8") (pintype "passive"))
      (node (ref "IC9") (pin "33") (pinfunction "GND_33") (pintype "passive"))
      (node (ref "J7") (pin "17") (pinfunction "DDC/CEC_Ground_17") (pintype "power_in"))
      (node (ref "L7") (pin "1") (pintype "passive"))
      (node (ref "R100") (pin "1") (pintype "passive"))
      (node (ref "R104") (pin "1") (pintype "passive"))
      (node (ref "R105") (pin "1") (pintype "passive"))
      (node (ref "R106") (pin "1") (pintype "passive"))
      (node (ref "R22") (pin "2") (pintype "passive"))
      (node (ref "R4") (pin "2") (pintype "passive"))
      (node (ref "R5") (pin "2") (pintype "passive"))
      (node (ref "R62") (pin "1") (pintype "passive"))
      (node (ref "R63") (pin "2") (pintype "passive"))
      (node (ref "R64") (pin "2") (pintype "passive"))
      (node (ref "R65") (pin "2") (pintype "passive"))
      (node (ref "R66") (pin "1") (pintype "passive"))
      (node (ref "R98") (pin "1") (pintype "passive"))
      (node (ref "R99") (pin "1") (pintype "passive"))
    )
    (net (code "61") (name "Net-(D1-PadA)") (class "Default")
      (node (ref "D1") (pin "A") (pinfunction "A_A") (pintype "passive"))
      (node (ref "L1") (pin "2") (pintype "passive"))
    )
    (net (code "62") (name "Net-(IC2-DDC_EN)") (class "Default")
      (node (ref "IC2") (pin "22") (pinfunction "DDC_EN_22") (pintype "passive"))
      (node (ref "R5") (pin "1") (pintype "passive"))
    )
    (net (code "63") (name "Net-(IC2-DDET)") (class "Default")
      (node (ref "IC2") (pin "3") (pinfunction "DDET_3") (pintype "passive"))
      (node (ref "R97") (pin "1") (pintype "passive"))
      (node (ref "R98") (pin "2") (pintype "passive"))
    )
    (net (code "64") (name "Net-(IC2-EQ_0)") (class "Default")
      (node (ref "IC2") (pin "8") (pinfunction "EQ_0_8") (pintype "passive"))
      (node (ref "R95") (pin "1") (pintype "passive"))
      (node (ref "R99") (pin "2") (pintype "passive"))
    )
    (net (code "65") (name "Net-(IC2-EQ_1)") (class "Default")
      (node (ref "IC2") (pin "2") (pinfunction "EQ_1_2") (pintype "passive"))
      (node (ref "R100") (pin "2") (pintype "passive"))
      (node (ref "R96") (pin "1") (pintype "passive"))
    )
    (net (code "66") (name "Net-(IC2-HIZ_EN)") (class "Default")
      (node (ref "IC2") (pin "24") (pinfunction "HIZ_EN_24") (pintype "passive"))
      (node (ref "R4") (pin "1") (pintype "passive"))
    )
    (net (code "67") (name "Net-(IC2-HPD_SNK)") (class "Default")
      (node (ref "IC2") (pin "17") (pinfunction "OE_N_17") (pintype "passive"))
      (node (ref "IC2") (pin "21") (pinfunction "HPD_SNK_21") (pintype "passive"))
      (node (ref "R22") (pin "1") (pintype "passive"))
      (node (ref "R88") (pin "2") (pintype "passive"))
    )
    (net (code "68") (name "Net-(IC2-REXT)") (class "Default")
      (node (ref "IC2") (pin "4") (pinfunction "REXT_4") (pintype "passive"))
      (node (ref "R62") (pin "2") (pintype "passive"))
    )
    (net (code "69") (name "Net-(IC9-DDC_EN)") (class "Default")
      (node (ref "IC9") (pin "22") (pinfunction "DDC_EN_22") (pintype "passive"))
      (node (ref "R64") (pin "1") (pintype "passive"))
    )
    (net (code "70") (name "Net-(IC9-DDET)") (class "Default")
      (node (ref "IC9") (pin "3") (pinfunction "DDET_3") (pintype "passive"))
      (node (ref "R103") (pin "1") (pintype "passive"))
      (node (ref "R104") (pin "2") (pintype "passive"))
    )
    (net (code "71") (name "Net-(IC9-EQ_0)") (class "Default")
      (node (ref "IC9") (pin "8") (pinfunction "EQ_0_8") (pintype "passive"))
      (node (ref "R101") (pin "1") (pintype "passive"))
      (node (ref "R105") (pin "2") (pintype "passive"))
    )
    (net (code "72") (name "Net-(IC9-EQ_1)") (class "Default")
      (node (ref "IC9") (pin "2") (pinfunction "EQ_1_2") (pintype "passive"))
      (node (ref "R102") (pin "1") (pintype "passive"))
      (node (ref "R106") (pin "2") (pintype "passive"))
    )
    (net (code "73") (name "Net-(IC9-HIZ_EN)") (class "Default")
      (node (ref "IC9") (pin "24") (pinfunction "HIZ_EN_24") (pintype "passive"))
      (node (ref "R63") (pin "1") (pintype "passive"))
    )
    (net (code "74") (name "Net-(IC9-HPD_SNK)") (class "Default")
      (node (ref "IC9") (pin "17") (pinfunction "OE_N_17") (pintype "passive"))
      (node (ref "IC9") (pin "21") (pinfunction "HPD_SNK_21") (pintype "passive"))
      (node (ref "R65") (pin "1") (pintype "passive"))
      (node (ref "R89") (pin "2") (pintype "passive"))
    )
    (net (code "75") (name "Net-(IC9-REXT)") (class "Default")
      (node (ref "IC9") (pin "4") (pinfunction "REXT_4") (pintype "passive"))
      (node (ref "R66") (pin "2") (pintype "passive"))
    )
    (net (code "76") (name "Net-(J7-CEC)") (class "Default")
      (node (ref "J7") (pin "13") (pinfunction "CEC_13") (pintype "passive"))
      (node (ref "TP1") (pin "1") (pintype "passive"))
    )
    (net (code "77") (name "Net-(J7-Hot_Plug_Detect)") (class "Default")
      (node (ref "J7") (pin "19") (pinfunction "Hot_Plug_Detect_19") (pintype "output"))
      (node (ref "TP2") (pin "1") (pintype "passive"))
    )
    (net (code "78") (name "SHIELD2") (class "Default")
      (node (ref "J7") (pin "11") (pinfunction "TMDS_Clock_Shield_11") (pintype "passive"))
      (node (ref "J7") (pin "2") (pinfunction "TMDS_Data2_Shield_2") (pintype "passive"))
      (node (ref "J7") (pin "5") (pinfunction "TMDS_Data1_Shield_5") (pintype "passive"))
      (node (ref "J7") (pin "8") (pinfunction "TMDS_Data0_Shield_8") (pintype "passive"))
      (node (ref "J7") (pin "S") (pinfunction "SH_S") (pintype "passive"))
      (node (ref "L7") (pin "2") (pintype "passive"))
    )
    (net (code "79") (name "unconnected-(IC2-HPD_SRC-Pad5)") (class "Default")
      (node (ref "IC2") (pin "5") (pinfunction "HPD_SRC_5") (pintype "passive+no_connect"))
    )
    (net (code "80") (name "unconnected-(IC2-SCL_SNK-Pad19)") (class "Default")
      (node (ref "IC2") (pin "19") (pinfunction "SCL_SNK_19") (pintype "passive+no_connect"))
    )
    (net (code "81") (name "unconnected-(IC2-SCL_SRC-Pad7)") (class "Default")
      (node (ref "IC2") (pin "7") (pinfunction "SCL_SRC_7") (pintype "passive+no_connect"))
    )
    (net (code "82") (name "unconnected-(IC2-SDA_SNK-Pad20)") (class "Default")
      (node (ref "IC2") (pin "20") (pinfunction "SDA_SNK_20") (pintype "passive+no_connect"))
    )
    (net (code "83") (name "unconnected-(IC2-SDA_SRC-Pad6)") (class "Default")
      (node (ref "IC2") (pin "6") (pinfunction "SDA_SRC_6") (pintype "passive+no_connect"))
    )
    (net (code "84") (name "unconnected-(IC9-HPD_SRC-Pad5)") (class "Default")
      (node (ref "IC9") (pin "5") (pinfunction "HPD_SRC_5") (pintype "passive+no_connect"))
    )
    (net (code "85") (name "unconnected-(IC9-SCL_SNK-Pad19)") (class "Default")
      (node (ref "IC9") (pin "19") (pinfunction "SCL_SNK_19") (pintype "passive+no_connect"))
    )
    (net (code "86") (name "unconnected-(IC9-SCL_SRC-Pad7)") (class "Default")
      (node (ref "IC9") (pin "7") (pinfunction "SCL_SRC_7") (pintype "passive+no_connect"))
    )
    (net (code "87") (name "unconnected-(IC9-SDA_SNK-Pad20)") (class "Default")
      (node (ref "IC9") (pin "20") (pinfunction "SDA_SNK_20") (pintype "passive+no_connect"))
    )
    (net (code "88") (name "unconnected-(IC9-SDA_SRC-Pad6)") (class "Default")
      (node (ref "IC9") (pin "6") (pinfunction "SDA_SRC_6") (pintype "passive+no_connect"))
    )
    (net (code "89") (name "unconnected-(J7-SCL-Pad15)") (class "Default")
      (node (ref "J7") (pin "15") (pinfunction "SCL_15") (pintype "bidirectional+no_connect"))
    )
    (net (code "90") (name "unconnected-(J7-SDA-Pad16)") (class "Default")
      (node (ref "J7") (pin "16") (pinfunction "SDA_16") (pintype "bidirectional+no_connect"))
    )
    (net (code "91") (name "unconnected-(J7-Utility-Pad14)") (class "Default")
      (node (ref "J7") (pin "14") (pinfunction "Utility_14") (pintype "passive+no_connect"))
    )
  )
)
